# SCH_ESP_Weather_Cube_Enhanced_2022-10-04.net
KiCad netlist of a schematic drawn in EasyEDA
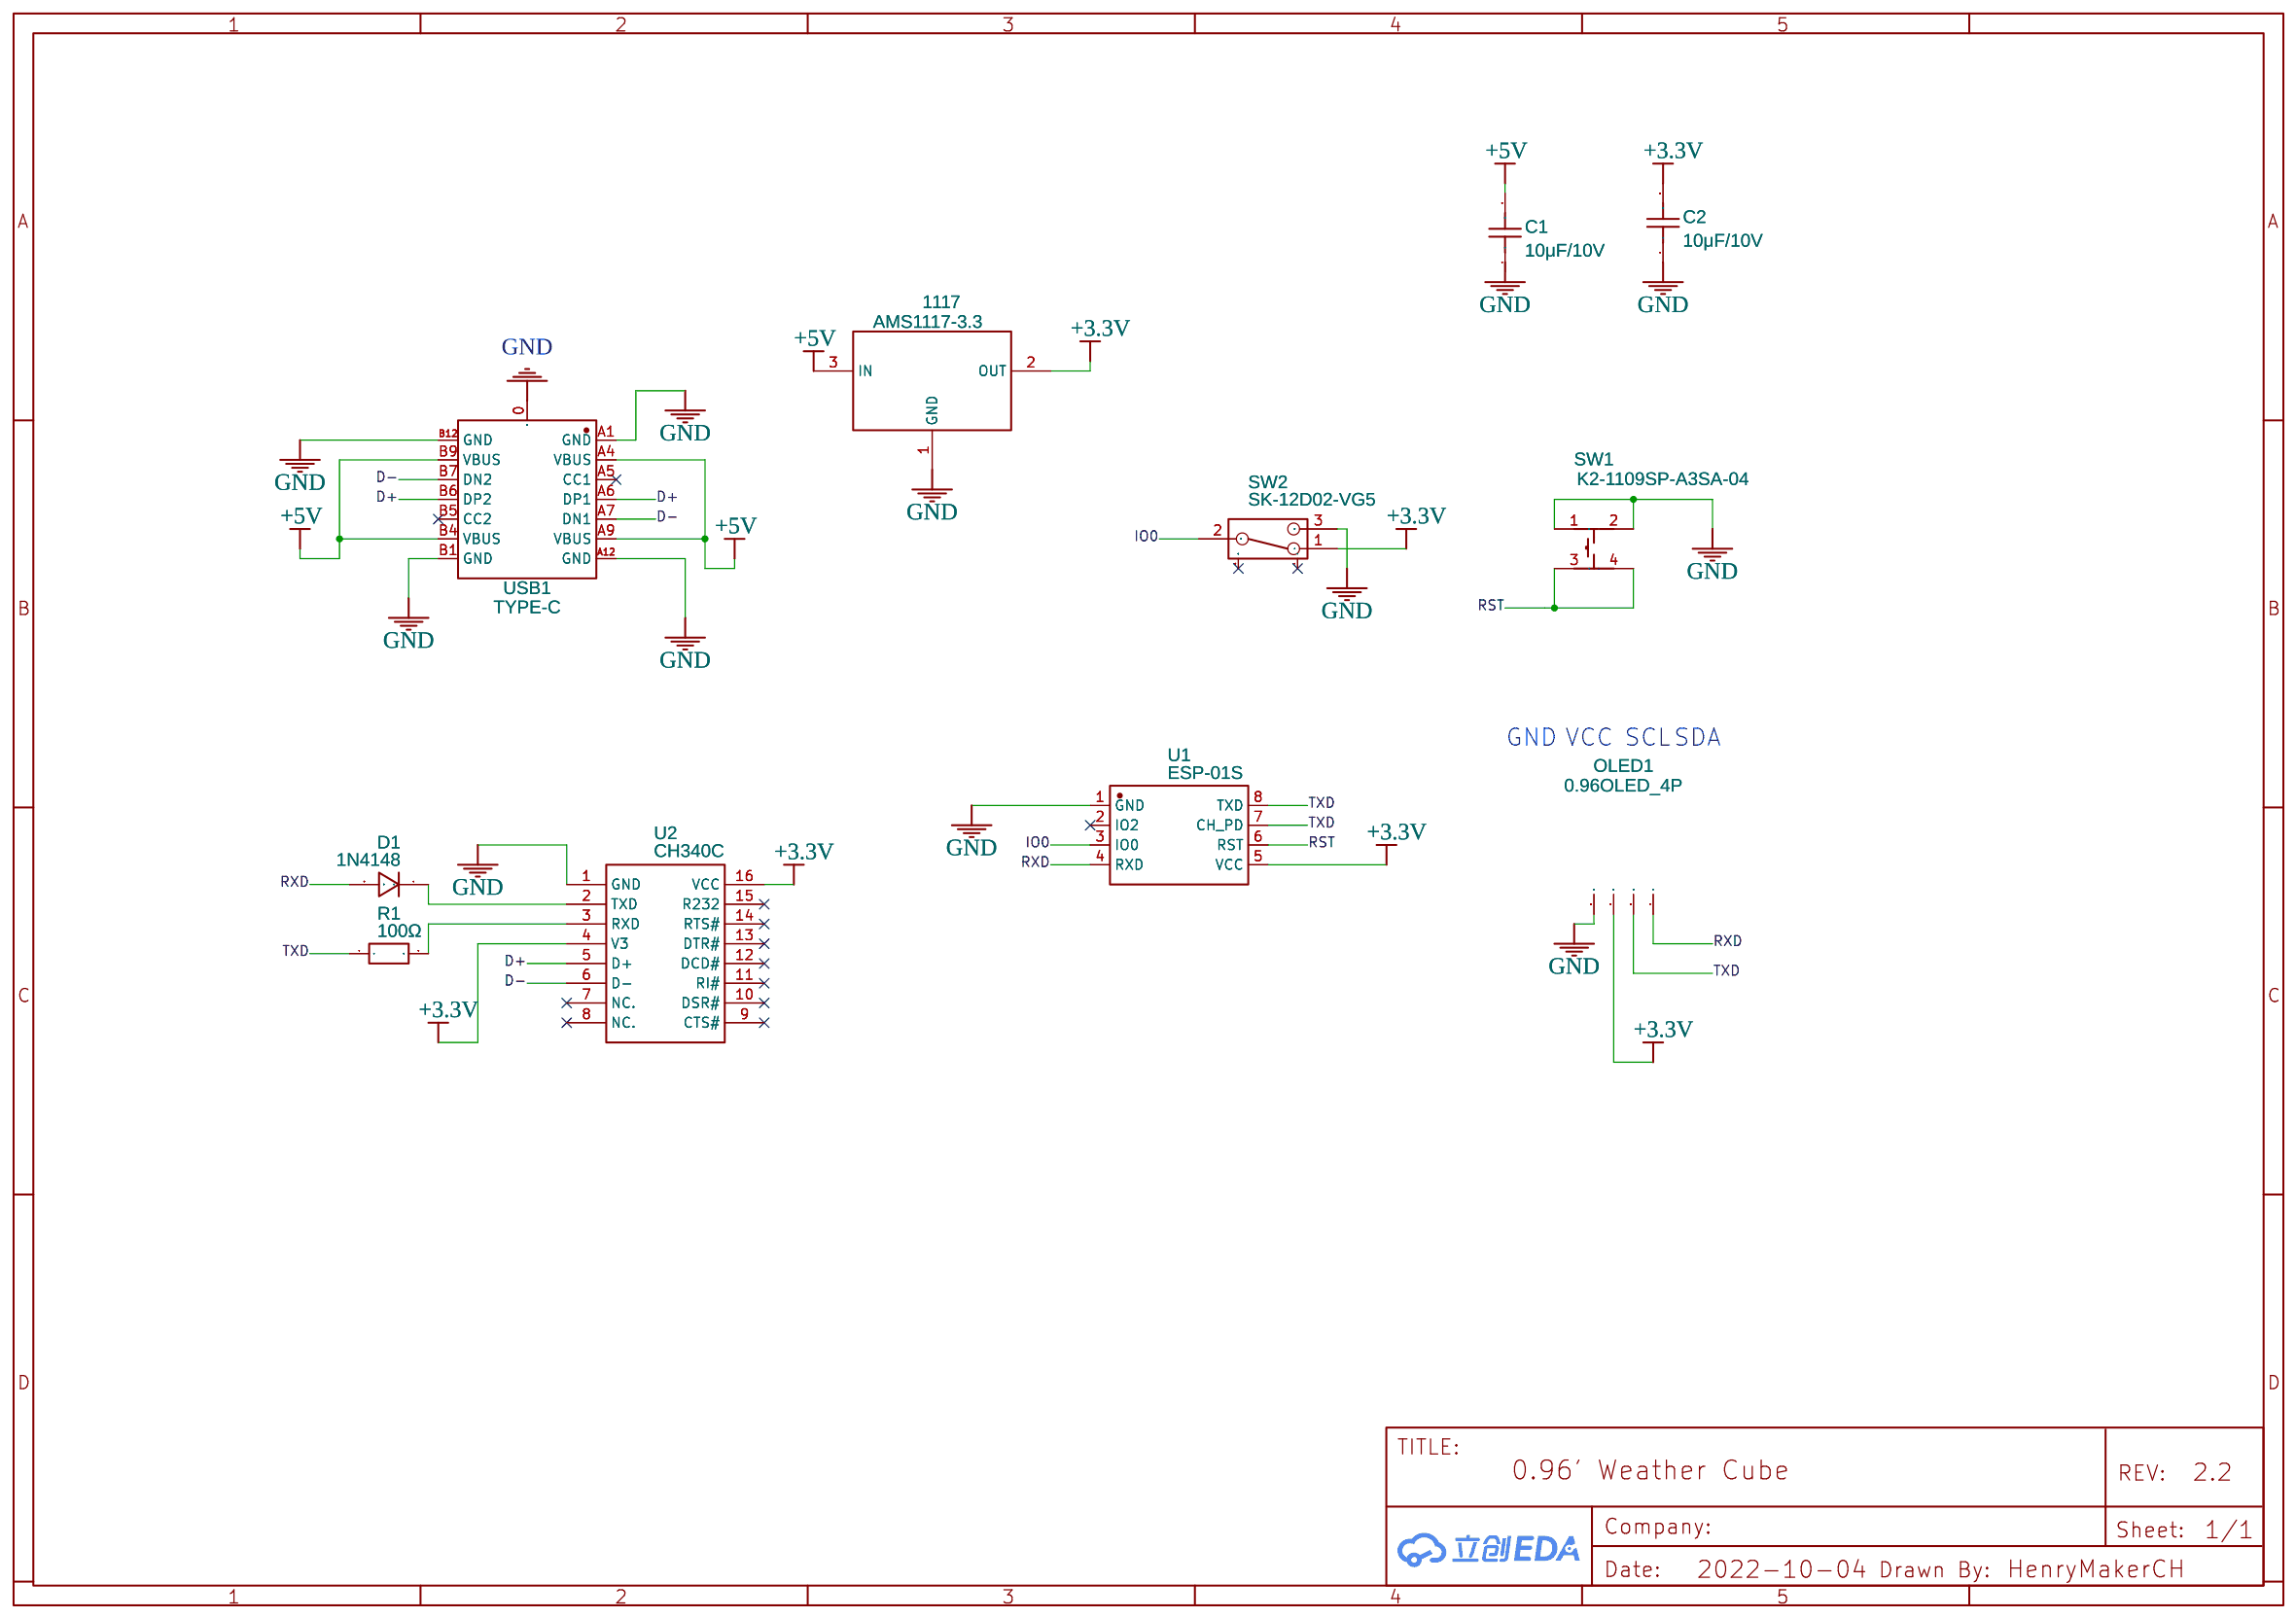
[diagram p0: schematic sheet]

(export (version "E")
  (design (tool "Eeschema 10.0.6"))
  (components
    (comp (ref "1117") (value "AMS1117-3.3") (libsource (lib "") (part "Unknown_425_-645")))
    (comp (ref "C1") (value "10μF/10V") (libsource (lib "") (part "Capacitor")))
    (comp (ref "C2") (value "10μF/10V") (libsource (lib "") (part "Capacitor")))
    (comp (ref "D1")
      (value "1N4148")
      (fields (field (name "BOM_Supplier Part") "C13769"))
      (libsource (lib "") (part "1N4148_C13769"))
    )
    (comp (ref "OLED1") (value "0.96OLED_4P") (libsource (lib "") (part "0.96OLED_4P")))
    (comp (ref "R1") (value "100Ω") (libsource (lib "") (part "R_0603_EU")))
    (comp (ref "SW1")
      (value "K2-1109SP-A3SA-04")
      (fields (field (name "BOM_Supplier Part") "C516447"))
      (libsource (lib "") (part "K2-1109SP-A3SA-04"))
    )
    (comp (ref "SW2")
      (value "SK-12D02-VG5")
      (fields (field (name "BOM_Supplier Part") "C136722"))
      (libsource (lib "") (part "SK-12D02-VG5"))
    )
    (comp (ref "U1")
      (value "ESP-01S")
      (fields (field (name "BOM_Supplier Part") "C111009"))
      (libsource (lib "") (part "ESP-01S"))
    )
    (comp (ref "U2")
      (value "CH340C")
      (fields (field (name "BOM_Supplier Part") "C84681"))
      (libsource (lib "") (part "CH340C"))
    )
    (comp (ref "USB1")
      (value "TYPE-C")
      (fields
        (field (name "BOM_Manufacturer Part") "TYPE-C-14M-015-100")
        (field (name "BOM_Supplier Part") "C2798183")
      )
      (libsource (lib "") (part "TYPE-C-14M-015-100"))
    )
  )
  (nets
    (net (code "1") (name "+3.3V") (class "Default")
      (node (ref "1117") (pin "2") (pinfunction "OUT_2") (pintype "unspecified"))
      (node (ref "C2") (pin "2") (pinfunction "2_2") (pintype "unspecified"))
      (node (ref "OLED1") (pin "2") (pinfunction "2_2") (pintype "unspecified"))
      (node (ref "SW2") (pin "1") (pinfunction "1_1") (pintype "unspecified"))
      (node (ref "U1") (pin "5") (pinfunction "VCC_5") (pintype "unspecified"))
      (node (ref "U2") (pin "16") (pinfunction "VCC_16") (pintype "unspecified"))
      (node (ref "U2") (pin "4") (pinfunction "V3_4") (pintype "unspecified"))
    )
    (net (code "2") (name "+5V") (class "Default")
      (node (ref "1117") (pin "3") (pinfunction "IN_3") (pintype "unspecified"))
      (node (ref "C1") (pin "2") (pinfunction "2_2") (pintype "unspecified"))
      (node (ref "USB1") (pin "A4") (pinfunction "VBUS_A4") (pintype "unspecified"))
      (node (ref "USB1") (pin "A9") (pinfunction "VBUS_A9") (pintype "unspecified"))
      (node (ref "USB1") (pin "B4") (pinfunction "VBUS_B4") (pintype "unspecified"))
      (node (ref "USB1") (pin "B9") (pinfunction "VBUS_B9") (pintype "unspecified"))
    )
    (net (code "3") (name "/D+") (class "Default")
      (node (ref "U2") (pin "5") (pinfunction "D+_5") (pintype "unspecified"))
      (node (ref "USB1") (pin "A6") (pinfunction "DP1_A6") (pintype "unspecified"))
      (node (ref "USB1") (pin "B6") (pinfunction "DP2_B6") (pintype "unspecified"))
    )
    (net (code "4") (name "/D-") (class "Default")
      (node (ref "U2") (pin "6") (pinfunction "D-_6") (pintype "unspecified"))
      (node (ref "USB1") (pin "A7") (pinfunction "DN1_A7") (pintype "unspecified"))
      (node (ref "USB1") (pin "B7") (pinfunction "DN2_B7") (pintype "unspecified"))
    )
    (net (code "5") (name "/IO0") (class "Default")
      (node (ref "SW2") (pin "2") (pinfunction "2_2") (pintype "unspecified"))
      (node (ref "U1") (pin "3") (pinfunction "IO0_3") (pintype "unspecified"))
    )
    (net (code "6") (name "/RST") (class "Default")
      (node (ref "SW1") (pin "3") (pinfunction "3_3") (pintype "unspecified"))
      (node (ref "SW1") (pin "4") (pinfunction "4_4") (pintype "unspecified"))
      (node (ref "U1") (pin "6") (pinfunction "RST_6") (pintype "unspecified"))
    )
    (net (code "7") (name "/RXD") (class "Default")
      (node (ref "D1") (pin "2") (pinfunction "2_2") (pintype "unspecified"))
      (node (ref "OLED1") (pin "4") (pinfunction "4_4") (pintype "unspecified"))
      (node (ref "U1") (pin "4") (pinfunction "RXD_4") (pintype "unspecified"))
    )
    (net (code "8") (name "/TXD") (class "Default")
      (node (ref "OLED1") (pin "3") (pinfunction "3_3") (pintype "unspecified"))
      (node (ref "R1") (pin "1") (pinfunction "1_1") (pintype "unspecified"))
      (node (ref "U1") (pin "7") (pinfunction "CH_PD_7") (pintype "unspecified"))
      (node (ref "U1") (pin "8") (pinfunction "TXD_8") (pintype "unspecified"))
    )
    (net (code "9") (name "GND") (class "Default")
      (node (ref "1117") (pin "1") (pinfunction "GND_1") (pintype "unspecified"))
      (node (ref "C1") (pin "1") (pinfunction "1_1") (pintype "unspecified"))
      (node (ref "C2") (pin "1") (pinfunction "1_1") (pintype "unspecified"))
      (node (ref "OLED1") (pin "1") (pinfunction "1_1") (pintype "unspecified"))
      (node (ref "SW1") (pin "1") (pinfunction "1_1") (pintype "unspecified"))
      (node (ref "SW1") (pin "2") (pinfunction "2_2") (pintype "unspecified"))
      (node (ref "SW2") (pin "3") (pinfunction "3_3") (pintype "unspecified"))
      (node (ref "U1") (pin "1") (pinfunction "GND_1") (pintype "unspecified"))
      (node (ref "U2") (pin "1") (pinfunction "GND_1") (pintype "unspecified"))
      (node (ref "USB1") (pin "0") (pinfunction "0_0") (pintype "unspecified"))
      (node (ref "USB1") (pin "A1") (pinfunction "GND_A1") (pintype "unspecified"))
      (node (ref "USB1") (pin "A12") (pinfunction "GND_A12") (pintype "unspecified"))
      (node (ref "USB1") (pin "B1") (pinfunction "GND_B1") (pintype "unspecified"))
      (node (ref "USB1") (pin "B12") (pinfunction "GND_B12") (pintype "unspecified"))
    )
    (net (code "10") (name "Net-(U2-RXD)") (class "Default")
      (node (ref "R1") (pin "2") (pinfunction "2_2") (pintype "unspecified"))
      (node (ref "U2") (pin "3") (pinfunction "RXD_3") (pintype "unspecified"))
    )
    (net (code "11") (name "Net-(U2-TXD)") (class "Default")
      (node (ref "D1") (pin "1") (pinfunction "1_1") (pintype "unspecified"))
      (node (ref "U2") (pin "2") (pinfunction "TXD_2") (pintype "unspecified"))
    )
    (net (code "12") (name "unconnected-(SW2-Pad4)") (class "Default")
      (node (ref "SW2") (pin "4") (pinfunction "4_4") (pintype "unspecified+no_connect"))
    )
    (net (code "13") (name "unconnected-(SW2-Pad5)") (class "Default")
      (node (ref "SW2") (pin "5") (pinfunction "5_5") (pintype "unspecified+no_connect"))
    )
    (net (code "14") (name "unconnected-(U1-IO2-Pad2)") (class "Default")
      (node (ref "U1") (pin "2") (pinfunction "IO2_2") (pintype "unspecified+no_connect"))
    )
    (net (code "15") (name "unconnected-(U2-CTS#-Pad9)") (class "Default")
      (node (ref "U2") (pin "9") (pinfunction "CTS#_9") (pintype "unspecified+no_connect"))
    )
    (net (code "16") (name "unconnected-(U2-DCD#-Pad12)") (class "Default")
      (node (ref "U2") (pin "12") (pinfunction "DCD#_12") (pintype "unspecified+no_connect"))
    )
    (net (code "17") (name "unconnected-(U2-DSR#-Pad10)") (class "Default")
      (node (ref "U2") (pin "10") (pinfunction "DSR#_10") (pintype "unspecified+no_connect"))
    )
    (net (code "18") (name "unconnected-(U2-DTR#-Pad13)") (class "Default")
      (node (ref "U2") (pin "13") (pinfunction "DTR#_13") (pintype "unspecified+no_connect"))
    )
    (net (code "19") (name "unconnected-(U2-NC.-Pad7)") (class "Default")
      (node (ref "U2") (pin "7") (pinfunction "NC._7") (pintype "unspecified+no_connect"))
    )
    (net (code "20") (name "unconnected-(U2-NC.-Pad8)") (class "Default")
      (node (ref "U2") (pin "8") (pinfunction "NC._8") (pintype "unspecified+no_connect"))
    )
    (net (code "21") (name "unconnected-(U2-R232-Pad15)") (class "Default")
      (node (ref "U2") (pin "15") (pinfunction "R232_15") (pintype "unspecified+no_connect"))
    )
    (net (code "22") (name "unconnected-(U2-RI#-Pad11)") (class "Default")
      (node (ref "U2") (pin "11") (pinfunction "RI#_11") (pintype "unspecified+no_connect"))
    )
    (net (code "23") (name "unconnected-(U2-RTS#-Pad14)") (class "Default")
      (node (ref "U2") (pin "14") (pinfunction "RTS#_14") (pintype "unspecified+no_connect"))
    )
    (net (code "24") (name "unconnected-(USB1-CC1-PadA5)") (class "Default")
      (node (ref "USB1") (pin "A5") (pinfunction "CC1_A5") (pintype "unspecified+no_connect"))
    )
    (net (code "25") (name "unconnected-(USB1-CC2-PadB5)") (class "Default")
      (node (ref "USB1") (pin "B5") (pinfunction "CC2_B5") (pintype "unspecified+no_connect"))
    )
  )
)
